# powerboard.net
KiCad netlist of a schematic drawn in EAGLE
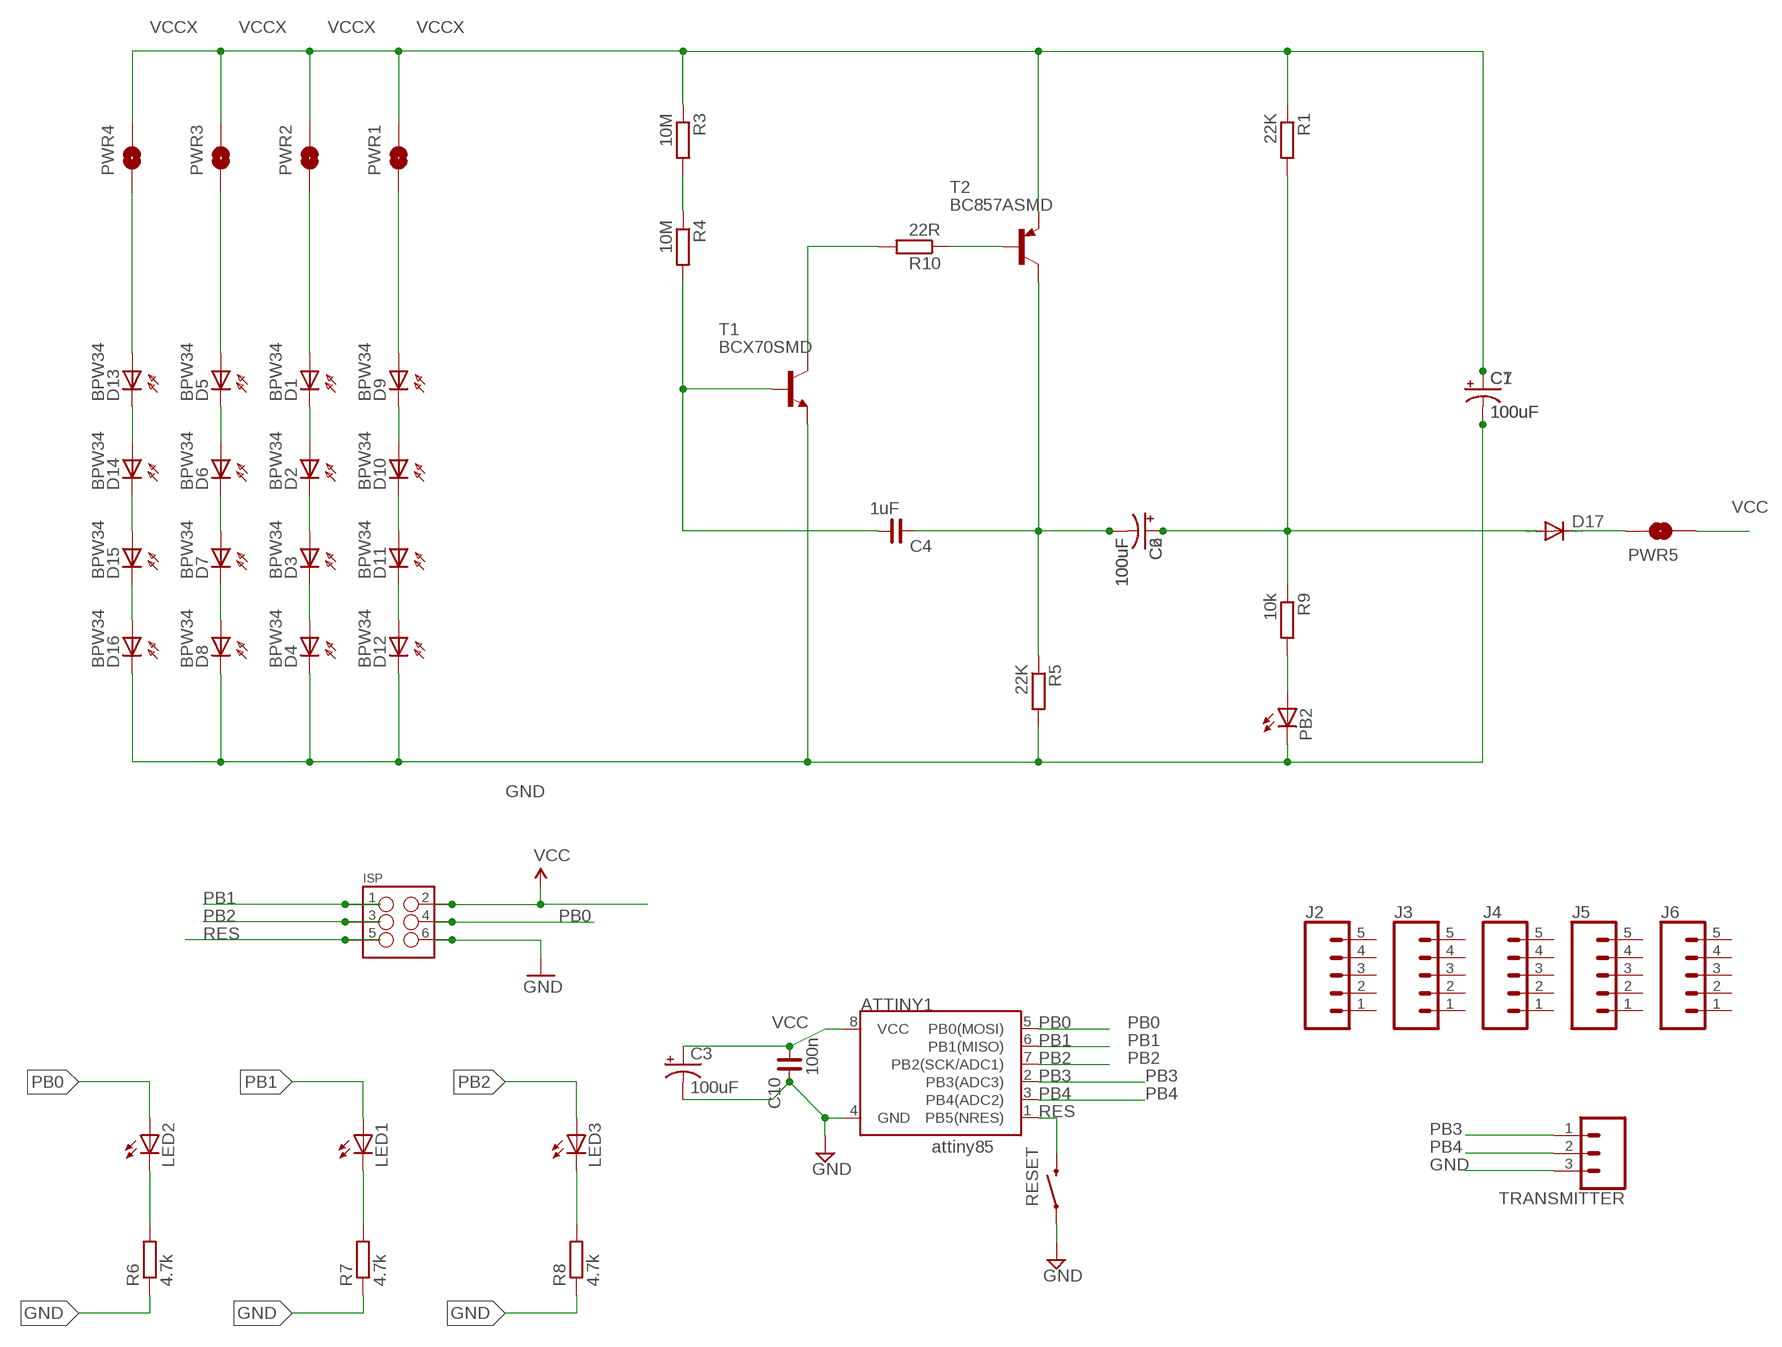
[diagram p0: schematic, sheet 1]

(export (version "E")
  (design (tool "Eeschema 10.0.6"))
  (components
    (comp (ref "ATTINY1")
      (value "ATTINY45DIP8")
      (footprint "eagle-import:DIP08")
      (libsource (lib "eagle-import") (part "ATTINY45DIP8"))
    )
    (comp (ref "C1")
      (value "100uF")
      (footprint "eagle-import:CPOL-RADIAL-10UF-25V")
      (libsource (lib "eagle-import") (part "CAP_POLPTH2"))
    )
    (comp (ref "C2")
      (value "100uF")
      (footprint "eagle-import:CPOL-RADIAL-10UF-25V")
      (libsource (lib "eagle-import") (part "CAP_POLPTH2"))
    )
    (comp (ref "C3")
      (value "100uF")
      (footprint "eagle-import:CPOL-RADIAL-10UF-25V")
      (libsource (lib "eagle-import") (part "CAP_POLPTH2"))
    )
    (comp (ref "C4")
      (value "1uF")
      (footprint "eagle-import:C0805")
      (libsource (lib "eagle-import") (part "C_0805"))
    )
    (comp (ref "C6")
      (value "100uF")
      (footprint "eagle-import:EIA3216")
      (libsource (lib "eagle-import") (part "CAP_POL1206"))
    )
    (comp (ref "C7")
      (value "100uF")
      (footprint "eagle-import:EIA3216")
      (libsource (lib "eagle-import") (part "CAP_POL1206"))
    )
    (comp (ref "C10")
      (value "100n")
      (footprint "eagle-import:C1206")
      (libsource (lib "eagle-import") (part "C_1206"))
    )
    (comp (ref "D1")
      (value "BPW34")
      (footprint "eagle-import:BP104")
      (libsource (lib "eagle-import") (part "BP104"))
    )
    (comp (ref "D2")
      (value "BPW34")
      (footprint "eagle-import:BP104")
      (libsource (lib "eagle-import") (part "BP104"))
    )
    (comp (ref "D3")
      (value "BPW34")
      (footprint "eagle-import:BP104")
      (libsource (lib "eagle-import") (part "BP104"))
    )
    (comp (ref "D4")
      (value "BPW34")
      (footprint "eagle-import:BP104")
      (libsource (lib "eagle-import") (part "BP104"))
    )
    (comp (ref "D5")
      (value "BPW34")
      (footprint "eagle-import:BP104")
      (libsource (lib "eagle-import") (part "BP104"))
    )
    (comp (ref "D6")
      (value "BPW34")
      (footprint "eagle-import:BP104")
      (libsource (lib "eagle-import") (part "BP104"))
    )
    (comp (ref "D7")
      (value "BPW34")
      (footprint "eagle-import:BP104")
      (libsource (lib "eagle-import") (part "BP104"))
    )
    (comp (ref "D8")
      (value "BPW34")
      (footprint "eagle-import:BP104")
      (libsource (lib "eagle-import") (part "BP104"))
    )
    (comp (ref "D9")
      (value "BPW34")
      (footprint "eagle-import:BP104")
      (libsource (lib "eagle-import") (part "BP104"))
    )
    (comp (ref "D10")
      (value "BPW34")
      (footprint "eagle-import:BP104")
      (libsource (lib "eagle-import") (part "BP104"))
    )
    (comp (ref "D11")
      (value "BPW34")
      (footprint "eagle-import:BP104")
      (libsource (lib "eagle-import") (part "BP104"))
    )
    (comp (ref "D12")
      (value "BPW34")
      (footprint "eagle-import:BP104")
      (libsource (lib "eagle-import") (part "BP104"))
    )
    (comp (ref "D13")
      (value "BPW34")
      (footprint "eagle-import:BP104")
      (libsource (lib "eagle-import") (part "BP104"))
    )
    (comp (ref "D14")
      (value "BPW34")
      (footprint "eagle-import:BP104")
      (libsource (lib "eagle-import") (part "BP104"))
    )
    (comp (ref "D15")
      (value "BPW34")
      (footprint "eagle-import:BP104")
      (libsource (lib "eagle-import") (part "BP104"))
    )
    (comp (ref "D16")
      (value "BPW34")
      (footprint "eagle-import:BP104")
      (libsource (lib "eagle-import") (part "BP104"))
    )
    (comp (ref "D17")
      (value "DIODE-DO214AA")
      (footprint "eagle-import:DO214AA")
      (libsource (lib "eagle-import") (part "DIODE-DO214AA"))
    )
    (comp (ref "ISP")
      (value "M03X2NO_SILK")
      (footprint "eagle-import:2X3-NS@1")
      (libsource (lib "eagle-import") (part "M03X2NO_SILK"))
    )
    (comp (ref "J2")
      (value "CONN_05NO_SILK")
      (footprint "eagle-import:1X05_NO_SILK")
      (libsource (lib "eagle-import") (part "CONN_05NO_SILK"))
    )
    (comp (ref "J3")
      (value "CONN_05NO_SILK")
      (footprint "eagle-import:1X05_NO_SILK")
      (libsource (lib "eagle-import") (part "CONN_05NO_SILK"))
    )
    (comp (ref "J4")
      (value "CONN_05NO_SILK")
      (footprint "eagle-import:1X05_NO_SILK")
      (libsource (lib "eagle-import") (part "CONN_05NO_SILK"))
    )
    (comp (ref "J5")
      (value "CONN_05NO_SILK")
      (footprint "eagle-import:1X05_NO_SILK")
      (libsource (lib "eagle-import") (part "CONN_05NO_SILK"))
    )
    (comp (ref "J6")
      (value "CONN_05NO_SILK")
      (footprint "eagle-import:1X05_NO_SILK")
      (libsource (lib "eagle-import") (part "CONN_05NO_SILK"))
    )
    (comp (ref "LED1")
      (value "LEDCHIPLED_1206")
      (footprint "eagle-import:CHIPLED_1206")
      (libsource (lib "eagle-import") (part "LEDCHIPLED_1206"))
    )
    (comp (ref "LED2")
      (value "LEDCHIPLED_1206")
      (footprint "eagle-import:CHIPLED_1206")
      (libsource (lib "eagle-import") (part "LEDCHIPLED_1206"))
    )
    (comp (ref "LED3")
      (value "LEDCHIPLED_1206")
      (footprint "eagle-import:CHIPLED_1206")
      (libsource (lib "eagle-import") (part "LEDCHIPLED_1206"))
    )
    (comp (ref "PB2")
      (value "LEDKA-3528ASYC")
      (footprint "eagle-import:KA-3528ASYC")
      (libsource (lib "eagle-import") (part "LEDKA-3528ASYC"))
    )
    (comp (ref "PWR1")
      (value "SOLDERJUMPERNO")
      (footprint "eagle-import:SJ_2S-NO")
      (libsource (lib "eagle-import") (part "SOLDERJUMPERNO"))
    )
    (comp (ref "PWR2")
      (value "SOLDERJUMPERNO")
      (footprint "eagle-import:SJ_2S-NO")
      (libsource (lib "eagle-import") (part "SOLDERJUMPERNO"))
    )
    (comp (ref "PWR3")
      (value "SOLDERJUMPERNO")
      (footprint "eagle-import:SJ_2S-NO")
      (libsource (lib "eagle-import") (part "SOLDERJUMPERNO"))
    )
    (comp (ref "PWR4")
      (value "SOLDERJUMPERNO")
      (footprint "eagle-import:SJ_2S-NO")
      (libsource (lib "eagle-import") (part "SOLDERJUMPERNO"))
    )
    (comp (ref "PWR5")
      (value "SOLDERJUMPERNO")
      (footprint "eagle-import:SJ_2S-NO")
      (libsource (lib "eagle-import") (part "SOLDERJUMPERNO"))
    )
    (comp (ref "R1")
      (value "22K")
      (footprint "eagle-import:R0805W")
      (libsource (lib "eagle-import") (part "resistor_R-EU_R0805W"))
    )
    (comp (ref "R3")
      (value "10M")
      (footprint "eagle-import:R0805W")
      (libsource (lib "eagle-import") (part "resistor_R-EU_R0805W"))
    )
    (comp (ref "R4")
      (value "10M")
      (footprint "eagle-import:R0805W")
      (libsource (lib "eagle-import") (part "resistor_R-EU_R0805W"))
    )
    (comp (ref "R5")
      (value "22K")
      (footprint "eagle-import:R0805W")
      (libsource (lib "eagle-import") (part "resistor_R-EU_R0805W"))
    )
    (comp (ref "R6")
      (value "4.7k")
      (footprint "eagle-import:R1206W")
      (libsource (lib "eagle-import") (part "R-EU_R1206W"))
    )
    (comp (ref "R7")
      (value "4.7k")
      (footprint "eagle-import:R1206W")
      (libsource (lib "eagle-import") (part "R-EU_R1206W"))
    )
    (comp (ref "R8")
      (value "4.7k")
      (footprint "eagle-import:R1206W")
      (libsource (lib "eagle-import") (part "R-EU_R1206W"))
    )
    (comp (ref "R9")
      (value "10k")
      (footprint "eagle-import:R0805W")
      (libsource (lib "eagle-import") (part "resistor_R-EU_R0805W"))
    )
    (comp (ref "R10")
      (value "22R")
      (footprint "eagle-import:R0805")
      (libsource (lib "eagle-import") (part "resistor_R-EU_R0805"))
    )
    (comp (ref "RESET")
      (value "SWITCH-MOMENTARY-2PTH")
      (footprint "eagle-import:TACTILE-PTH")
      (libsource (lib "eagle-import") (part "SWITCH-MOMENTARY-2PTH"))
    )
    (comp (ref "T1")
      (value "BCX70SMD")
      (footprint "eagle-import:SOT23")
      (libsource (lib "eagle-import") (part "BCX70SMD"))
    )
    (comp (ref "T2")
      (value "BC857ASMD")
      (footprint "eagle-import:SOT23-BEC")
      (libsource (lib "eagle-import") (part "BC857SMDA"))
    )
    (comp (ref "TRANSMITTER")
      (value "CONN_03LONGPADS")
      (footprint "eagle-import:1X03_LONGPADS")
      (libsource (lib "eagle-import") (part "CONN_03LONGPADS"))
    )
  )
  (nets
    (net (code "1") (name "/PB3") (class "Default")
      (node (ref "ATTINY1") (pin "2") (pinfunction "PB3(ADC3)_2") (pintype "bidirectional"))
      (node (ref "TRANSMITTER") (pin "1") (pinfunction "1_1") (pintype "passive"))
    )
    (net (code "2") (name "/PB4") (class "Default")
      (node (ref "ATTINY1") (pin "3") (pinfunction "PB4(ADC2)_3") (pintype "bidirectional"))
      (node (ref "TRANSMITTER") (pin "2") (pinfunction "2_2") (pintype "passive"))
    )
    (net (code "3") (name "/RES") (class "Default")
      (node (ref "ATTINY1") (pin "1") (pinfunction "PB5(NRES)_1") (pintype "bidirectional"))
      (node (ref "ISP") (pin "5") (pinfunction "5_5") (pintype "bidirectional"))
      (node (ref "RESET") (pin "3") (pinfunction "2_3") (pintype "passive"))
    )
    (net (code "4") (name "/VCCX") (class "Default")
      (node (ref "C1") (pin "1") (pinfunction "+_1") (pintype "passive"))
      (node (ref "C7") (pin "A") (pinfunction "+_A") (pintype "passive"))
      (node (ref "PWR1") (pin "2") (pinfunction "2_2") (pintype "passive"))
      (node (ref "PWR2") (pin "2") (pinfunction "2_2") (pintype "passive"))
      (node (ref "PWR3") (pin "2") (pinfunction "2_2") (pintype "passive"))
      (node (ref "PWR4") (pin "2") (pinfunction "2_2") (pintype "passive"))
      (node (ref "R1") (pin "1") (pinfunction "1_1") (pintype "passive"))
      (node (ref "R3") (pin "1") (pinfunction "1_1") (pintype "passive"))
      (node (ref "T2") (pin "E") (pinfunction "E_E") (pintype "passive"))
    )
    (net (code "5") (name "GND") (class "Default")
      (node (ref "ATTINY1") (pin "4") (pinfunction "GND_4") (pintype "bidirectional"))
      (node (ref "C1") (pin "2") (pinfunction "-_2") (pintype "passive"))
      (node (ref "C10") (pin "2") (pinfunction "2_2") (pintype "passive"))
      (node (ref "C3") (pin "2") (pinfunction "-_2") (pintype "passive"))
      (node (ref "C7") (pin "C") (pinfunction "-_C") (pintype "passive"))
      (node (ref "D12") (pin "K") (pinfunction "C_K") (pintype "passive"))
      (node (ref "D16") (pin "K") (pinfunction "C_K") (pintype "passive"))
      (node (ref "D4") (pin "K") (pinfunction "C_K") (pintype "passive"))
      (node (ref "D8") (pin "K") (pinfunction "C_K") (pintype "passive"))
      (node (ref "ISP") (pin "6") (pinfunction "6_6") (pintype "bidirectional"))
      (node (ref "PB2") (pin "C") (pinfunction "C_C") (pintype "passive"))
      (node (ref "R5") (pin "2") (pinfunction "2_2") (pintype "passive"))
      (node (ref "R6") (pin "1") (pinfunction "1_1") (pintype "passive"))
      (node (ref "R7") (pin "1") (pinfunction "1_1") (pintype "passive"))
      (node (ref "R8") (pin "1") (pinfunction "1_1") (pintype "passive"))
      (node (ref "RESET") (pin "1") (pinfunction "1_1") (pintype "passive"))
      (node (ref "T1") (pin "2") (pinfunction "E_2") (pintype "passive"))
      (node (ref "TRANSMITTER") (pin "3") (pinfunction "3_3") (pintype "passive"))
    )
    (net (code "6") (name "Net-(C2-+)") (class "Default")
      (node (ref "C2") (pin "1") (pinfunction "+_1") (pintype "passive"))
      (node (ref "C6") (pin "A") (pinfunction "+_A") (pintype "passive"))
      (node (ref "D17") (pin "A") (pinfunction "A_A") (pintype "passive"))
      (node (ref "R1") (pin "2") (pinfunction "2_2") (pintype "passive"))
      (node (ref "R9") (pin "1") (pinfunction "1_1") (pintype "passive"))
    )
    (net (code "7") (name "Net-(C2--)") (class "Default")
      (node (ref "C2") (pin "2") (pinfunction "-_2") (pintype "passive"))
      (node (ref "C4") (pin "2") (pinfunction "2_2") (pintype "passive"))
      (node (ref "C6") (pin "C") (pinfunction "-_C") (pintype "passive"))
      (node (ref "R5") (pin "1") (pinfunction "1_1") (pintype "passive"))
      (node (ref "T2") (pin "C") (pinfunction "C_C") (pintype "passive"))
    )
    (net (code "8") (name "Net-(D1-C)") (class "Default")
      (node (ref "D1") (pin "K") (pinfunction "C_K") (pintype "passive"))
      (node (ref "D2") (pin "A") (pinfunction "A_A") (pintype "passive"))
    )
    (net (code "9") (name "Net-(D1-PadA)") (class "Default")
      (node (ref "D1") (pin "A") (pinfunction "A_A") (pintype "passive"))
      (node (ref "PWR2") (pin "1") (pinfunction "1_1") (pintype "passive"))
    )
    (net (code "10") (name "Net-(D2-C)") (class "Default")
      (node (ref "D2") (pin "K") (pinfunction "C_K") (pintype "passive"))
      (node (ref "D3") (pin "A") (pinfunction "A_A") (pintype "passive"))
    )
    (net (code "11") (name "Net-(D3-C)") (class "Default")
      (node (ref "D3") (pin "K") (pinfunction "C_K") (pintype "passive"))
      (node (ref "D4") (pin "A") (pinfunction "A_A") (pintype "passive"))
    )
    (net (code "12") (name "Net-(D5-C)") (class "Default")
      (node (ref "D5") (pin "K") (pinfunction "C_K") (pintype "passive"))
      (node (ref "D6") (pin "A") (pinfunction "A_A") (pintype "passive"))
    )
    (net (code "13") (name "Net-(D5-PadA)") (class "Default")
      (node (ref "D5") (pin "A") (pinfunction "A_A") (pintype "passive"))
      (node (ref "PWR3") (pin "1") (pinfunction "1_1") (pintype "passive"))
    )
    (net (code "14") (name "Net-(D6-C)") (class "Default")
      (node (ref "D6") (pin "K") (pinfunction "C_K") (pintype "passive"))
      (node (ref "D7") (pin "A") (pinfunction "A_A") (pintype "passive"))
    )
    (net (code "15") (name "Net-(D7-C)") (class "Default")
      (node (ref "D7") (pin "K") (pinfunction "C_K") (pintype "passive"))
      (node (ref "D8") (pin "A") (pinfunction "A_A") (pintype "passive"))
    )
    (net (code "16") (name "Net-(D9-C)") (class "Default")
      (node (ref "D10") (pin "A") (pinfunction "A_A") (pintype "passive"))
      (node (ref "D9") (pin "K") (pinfunction "C_K") (pintype "passive"))
    )
    (net (code "17") (name "Net-(D9-PadA)") (class "Default")
      (node (ref "D9") (pin "A") (pinfunction "A_A") (pintype "passive"))
      (node (ref "PWR1") (pin "1") (pinfunction "1_1") (pintype "passive"))
    )
    (net (code "18") (name "Net-(D10-C)") (class "Default")
      (node (ref "D10") (pin "K") (pinfunction "C_K") (pintype "passive"))
      (node (ref "D11") (pin "A") (pinfunction "A_A") (pintype "passive"))
    )
    (net (code "19") (name "Net-(D11-C)") (class "Default")
      (node (ref "D11") (pin "K") (pinfunction "C_K") (pintype "passive"))
      (node (ref "D12") (pin "A") (pinfunction "A_A") (pintype "passive"))
    )
    (net (code "20") (name "Net-(D13-C)") (class "Default")
      (node (ref "D13") (pin "K") (pinfunction "C_K") (pintype "passive"))
      (node (ref "D14") (pin "A") (pinfunction "A_A") (pintype "passive"))
    )
    (net (code "21") (name "Net-(D13-PadA)") (class "Default")
      (node (ref "D13") (pin "A") (pinfunction "A_A") (pintype "passive"))
      (node (ref "PWR4") (pin "1") (pinfunction "1_1") (pintype "passive"))
    )
    (net (code "22") (name "Net-(D14-C)") (class "Default")
      (node (ref "D14") (pin "K") (pinfunction "C_K") (pintype "passive"))
      (node (ref "D15") (pin "A") (pinfunction "A_A") (pintype "passive"))
    )
    (net (code "23") (name "Net-(D15-C)") (class "Default")
      (node (ref "D15") (pin "K") (pinfunction "C_K") (pintype "passive"))
      (node (ref "D16") (pin "A") (pinfunction "A_A") (pintype "passive"))
    )
    (net (code "24") (name "Net-(D17-PadC)") (class "Default")
      (node (ref "D17") (pin "C") (pinfunction "C_C") (pintype "passive"))
      (node (ref "PWR5") (pin "2") (pinfunction "2_2") (pintype "passive"))
    )
    (net (code "25") (name "Net-(LED1-PadC)") (class "Default")
      (node (ref "LED1") (pin "C") (pinfunction "C_C") (pintype "passive"))
      (node (ref "R7") (pin "2") (pinfunction "2_2") (pintype "passive"))
    )
    (net (code "26") (name "Net-(LED2-PadC)") (class "Default")
      (node (ref "LED2") (pin "C") (pinfunction "C_C") (pintype "passive"))
      (node (ref "R6") (pin "2") (pinfunction "2_2") (pintype "passive"))
    )
    (net (code "27") (name "Net-(LED3-PadC)") (class "Default")
      (node (ref "LED3") (pin "C") (pinfunction "C_C") (pintype "passive"))
      (node (ref "R8") (pin "2") (pinfunction "2_2") (pintype "passive"))
    )
    (net (code "28") (name "Net-(PB2-PadA)") (class "Default")
      (node (ref "PB2") (pin "A") (pinfunction "A_A") (pintype "passive"))
      (node (ref "R9") (pin "2") (pinfunction "2_2") (pintype "passive"))
    )
    (net (code "29") (name "Net-(R3-Pad2)") (class "Default")
      (node (ref "R3") (pin "2") (pinfunction "2_2") (pintype "passive"))
      (node (ref "R4") (pin "1") (pinfunction "1_1") (pintype "passive"))
    )
    (net (code "30") (name "Net-(R10-Pad1)") (class "Default")
      (node (ref "R10") (pin "1") (pinfunction "1_1") (pintype "passive"))
      (node (ref "T2") (pin "B") (pinfunction "B_B") (pintype "passive"))
    )
    (net (code "31") (name "Net-(T1-B)") (class "Default")
      (node (ref "C4") (pin "1") (pinfunction "1_1") (pintype "passive"))
      (node (ref "R4") (pin "2") (pinfunction "2_2") (pintype "passive"))
      (node (ref "T1") (pin "1") (pinfunction "B_1") (pintype "passive"))
    )
    (net (code "32") (name "Net-(T1-C)") (class "Default")
      (node (ref "R10") (pin "2") (pinfunction "2_2") (pintype "passive"))
      (node (ref "T1") (pin "3") (pinfunction "C_3") (pintype "passive"))
    )
    (net (code "33") (name "PB0") (class "Default")
      (node (ref "ATTINY1") (pin "5") (pinfunction "PB0(MOSI)_5") (pintype "bidirectional"))
      (node (ref "ISP") (pin "4") (pinfunction "4_4") (pintype "bidirectional"))
      (node (ref "LED2") (pin "A") (pinfunction "A_A") (pintype "passive"))
    )
    (net (code "34") (name "PB1") (class "Default")
      (node (ref "ATTINY1") (pin "6") (pinfunction "PB1(MISO)_6") (pintype "bidirectional"))
      (node (ref "ISP") (pin "1") (pinfunction "1_1") (pintype "bidirectional"))
      (node (ref "LED1") (pin "A") (pinfunction "A_A") (pintype "passive"))
    )
    (net (code "35") (name "PB2") (class "Default")
      (node (ref "ATTINY1") (pin "7") (pinfunction "PB2(SCK/ADC1)_7") (pintype "bidirectional"))
      (node (ref "ISP") (pin "3") (pinfunction "3_3") (pintype "bidirectional"))
      (node (ref "LED3") (pin "A") (pinfunction "A_A") (pintype "passive"))
    )
    (net (code "36") (name "VCC") (class "Default")
      (node (ref "ATTINY1") (pin "8") (pinfunction "VCC_8") (pintype "bidirectional"))
      (node (ref "C10") (pin "1") (pinfunction "1_1") (pintype "passive"))
      (node (ref "C3") (pin "1") (pinfunction "+_1") (pintype "passive"))
      (node (ref "ISP") (pin "2") (pinfunction "2_2") (pintype "bidirectional"))
      (node (ref "PWR5") (pin "1") (pinfunction "1_1") (pintype "passive"))
    )
    (net (code "37") (name "unconnected-(J2-Pad1)") (class "Default")
      (node (ref "J2") (pin "1") (pinfunction "1_1") (pintype "passive"))
    )
    (net (code "38") (name "unconnected-(J2-Pad2)") (class "Default")
      (node (ref "J2") (pin "2") (pinfunction "2_2") (pintype "passive"))
    )
    (net (code "39") (name "unconnected-(J2-Pad3)") (class "Default")
      (node (ref "J2") (pin "3") (pinfunction "3_3") (pintype "passive"))
    )
    (net (code "40") (name "unconnected-(J2-Pad4)") (class "Default")
      (node (ref "J2") (pin "4") (pinfunction "4_4") (pintype "passive"))
    )
    (net (code "41") (name "unconnected-(J2-Pad5)") (class "Default")
      (node (ref "J2") (pin "5") (pinfunction "5_5") (pintype "passive"))
    )
    (net (code "42") (name "unconnected-(J3-Pad1)") (class "Default")
      (node (ref "J3") (pin "1") (pinfunction "1_1") (pintype "passive"))
    )
    (net (code "43") (name "unconnected-(J3-Pad2)") (class "Default")
      (node (ref "J3") (pin "2") (pinfunction "2_2") (pintype "passive"))
    )
    (net (code "44") (name "unconnected-(J3-Pad3)") (class "Default")
      (node (ref "J3") (pin "3") (pinfunction "3_3") (pintype "passive"))
    )
    (net (code "45") (name "unconnected-(J3-Pad4)") (class "Default")
      (node (ref "J3") (pin "4") (pinfunction "4_4") (pintype "passive"))
    )
    (net (code "46") (name "unconnected-(J3-Pad5)") (class "Default")
      (node (ref "J3") (pin "5") (pinfunction "5_5") (pintype "passive"))
    )
    (net (code "47") (name "unconnected-(J4-Pad1)") (class "Default")
      (node (ref "J4") (pin "1") (pinfunction "1_1") (pintype "passive"))
    )
    (net (code "48") (name "unconnected-(J4-Pad2)") (class "Default")
      (node (ref "J4") (pin "2") (pinfunction "2_2") (pintype "passive"))
    )
    (net (code "49") (name "unconnected-(J4-Pad3)") (class "Default")
      (node (ref "J4") (pin "3") (pinfunction "3_3") (pintype "passive"))
    )
    (net (code "50") (name "unconnected-(J4-Pad4)") (class "Default")
      (node (ref "J4") (pin "4") (pinfunction "4_4") (pintype "passive"))
    )
    (net (code "51") (name "unconnected-(J4-Pad5)") (class "Default")
      (node (ref "J4") (pin "5") (pinfunction "5_5") (pintype "passive"))
    )
    (net (code "52") (name "unconnected-(J5-Pad1)") (class "Default")
      (node (ref "J5") (pin "1") (pinfunction "1_1") (pintype "passive"))
    )
    (net (code "53") (name "unconnected-(J5-Pad2)") (class "Default")
      (node (ref "J5") (pin "2") (pinfunction "2_2") (pintype "passive"))
    )
    (net (code "54") (name "unconnected-(J5-Pad3)") (class "Default")
      (node (ref "J5") (pin "3") (pinfunction "3_3") (pintype "passive"))
    )
    (net (code "55") (name "unconnected-(J5-Pad4)") (class "Default")
      (node (ref "J5") (pin "4") (pinfunction "4_4") (pintype "passive"))
    )
    (net (code "56") (name "unconnected-(J5-Pad5)") (class "Default")
      (node (ref "J5") (pin "5") (pinfunction "5_5") (pintype "passive"))
    )
    (net (code "57") (name "unconnected-(J6-Pad1)") (class "Default")
      (node (ref "J6") (pin "1") (pinfunction "1_1") (pintype "passive"))
    )
    (net (code "58") (name "unconnected-(J6-Pad2)") (class "Default")
      (node (ref "J6") (pin "2") (pinfunction "2_2") (pintype "passive"))
    )
    (net (code "59") (name "unconnected-(J6-Pad3)") (class "Default")
      (node (ref "J6") (pin "3") (pinfunction "3_3") (pintype "passive"))
    )
    (net (code "60") (name "unconnected-(J6-Pad4)") (class "Default")
      (node (ref "J6") (pin "4") (pinfunction "4_4") (pintype "passive"))
    )
    (net (code "61") (name "unconnected-(J6-Pad5)") (class "Default")
      (node (ref "J6") (pin "5") (pinfunction "5_5") (pintype "passive"))
    )
  )
)
